# POWER.net
KiCad netlist of a schematic drawn in Altium Designer
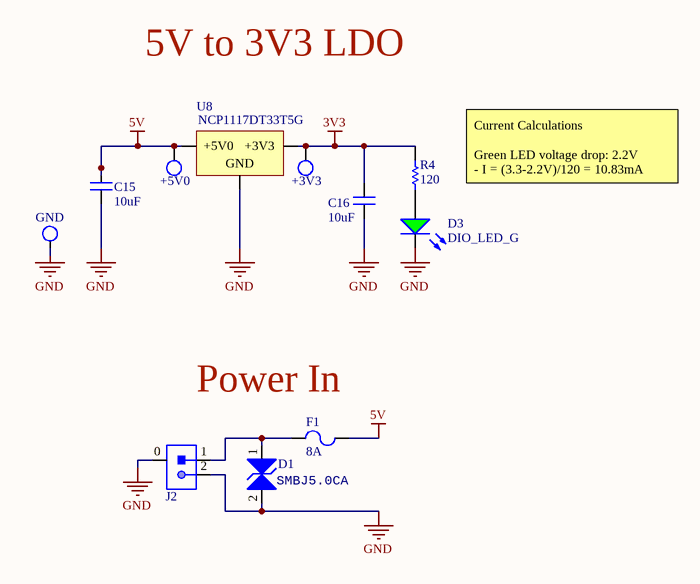
[diagram p0: POWER.SchDoc]

(export (version "E")
  (design (tool "Eeschema 10.0.6"))
  (components
    (comp (ref "+3V3")
      (value "TESTPOINT_LOOP")
      (footprint "TESTPOINT_LOOP")
      (description "Loop testpoint through-hole pad")
      (fields (field (name "MANUFACTURER") "Keystone Electronics"))
      (libsource (lib "UWRT_Schematic_Library_2020") (part "TESTPOINT_LOOP"))
    )
    (comp (ref "+5V0")
      (value "TESTPOINT_LOOP")
      (footprint "TESTPOINT_LOOP")
      (description "Loop testpoint through-hole pad")
      (fields (field (name "MANUFACTURER") "Keystone Electronics"))
      (libsource (lib "UWRT_Schematic_Library_2020") (part "TESTPOINT_LOOP"))
    )
    (comp (ref "C15")
      (value "10uF")
      (footprint "CAPC1206(3216)")
      (description "CAP CER 10UF 50V X5R 1206")
      (fields (field (name "MPN") "GRT31CR61H106KE01L") (field (name "MANUFACTURER") "Murata"))
      (libsource (lib "UWRT_Schematic_Library_2020") (part "CAP_10uF_50V_1206"))
    )
    (comp (ref "C16")
      (value "10uF")
      (footprint "CAPC1206(3216)")
      (description "CAP CER 10UF 50V X5R 1206")
      (fields (field (name "MPN") "GRT31CR61H106KE01L") (field (name "MANUFACTURER") "Murata"))
      (libsource (lib "UWRT_Schematic_Library_2020") (part "CAP_10uF_50V_1206"))
    )
    (comp (ref "D1")
      (value "TVS_DIODE_BIDIRECTIONAL")
      (footprint "TVS_DIODE_BIDIRECTIONAL")
      (description "TVS DIODE 5V 9.2V DO214AA")
      (fields
        (field (name "MANUFACTURER") "Nexperia USA Inc.")
        (field (name "MANUFACTURER PART NUMBER 1") "SMBJ5.0CA")
      )
      (libsource (lib "UWRT_Schematic_Library_2020") (part "TVS_DIODE_BIDIRECTIONAL"))
    )
    (comp (ref "D3")
      (value "DIO_LED_G")
      (footprint "LED_0805_LINE")
      (description "LED GREEN DIFFUSED 0805 SMD")
      (fields (field (name "MPN") "LG R971-KN-1") (field (name "MANUFACTURER") "OSRAM"))
      (libsource (lib "UWRT_Schematic_Library_2020") (part "DIO_LED_G"))
    )
    (comp (ref "F1")
      (value "FUSE_8A_1206")
      (footprint "FUSE_1206")
      (description "FUSE SMD 8A 24V")
      (fields (field (name "CURRENT RATING") "8A"))
      (libsource (lib "UWRT_Schematic_Library_2020") (part "FUSE_8A_1206"))
    )
    (comp (ref "GND")
      (value "TESTPOINT_LOOP")
      (footprint "TESTPOINT_LOOP")
      (description "Loop testpoint through-hole pad")
      (fields (field (name "MANUFACTURER") "Keystone Electronics"))
      (libsource (lib "UWRT_Schematic_Library_2020") (part "TESTPOINT_LOOP"))
    )
    (comp (ref "J2")
      (value "CON_2M_SM_RA")
      (footprint "MOLEX-5024940270")
      (description "CONN HEADER SMD RIGHT ANGLE 2MM PITCH")
      (libsource (lib "UWRT_Schematic_Library_2020") (part "CON_2M_SM_RA"))
    )
    (comp (ref "R4")
      (value "120")
      (footprint "RESC0603(1608)_N")
      (description "RES SMD 120 OHM 5% 1/10W 0603")
      (fields (field (name "TOLERANCE") "5%") (field (name "Comment") "RES_120R_0603"))
      (libsource (lib "UWRT_Schematic_Library_2020") (part "RES_120R_0603"))
    )
    (comp (ref "U8")
      (value "5V0_3V3_LDO")
      (footprint "VOLTAGE_REGULATOR")
      (description "IC REG LINEAR 3.3V 1A DPAK")
      (fields (field (name "MPN") "NCP1117DT33T5G") (field (name "MANUFACTURER") "ON Semiconductor"))
      (libsource (lib "UWRT_Schematic_Library_2020") (part "5V0_3V3_LDO"))
    )
  )
  (nets
    (net (code "1") (name "3V3") (class "Default")
      (node (ref "+3V3") (pin "1") (pintype "passive"))
      (node (ref "C16") (pin "2") (pinfunction "2_2") (pintype "passive"))
      (node (ref "R4") (pin "2") (pinfunction "2_2") (pintype "passive"))
      (node (ref "U8") (pin "2") (pinfunction "+3V3_2") (pintype "passive"))
    )
    (net (code "2") (name "5V") (class "Default")
      (node (ref "+5V0") (pin "1") (pintype "passive"))
      (node (ref "C15") (pin "2") (pinfunction "2_2") (pintype "passive"))
      (node (ref "F1") (pin "2") (pinfunction "2_2") (pintype "passive"))
      (node (ref "U8") (pin "3") (pinfunction "+5V0_3") (pintype "passive"))
    )
    (net (code "3") (name "GND") (class "Default")
      (node (ref "C15") (pin "1") (pinfunction "1_1") (pintype "passive"))
      (node (ref "C16") (pin "1") (pinfunction "1_1") (pintype "passive"))
      (node (ref "D1") (pin "2") (pinfunction "2_2") (pintype "passive"))
      (node (ref "D3") (pin "2") (pinfunction "K_2") (pintype "passive"))
      (node (ref "GND") (pin "1") (pintype "passive"))
      (node (ref "J2") (pin "0") (pinfunction "0_0") (pintype "passive"))
      (node (ref "J2") (pin "2") (pinfunction "2_2") (pintype "passive"))
      (node (ref "U8") (pin "1") (pinfunction "GND_1") (pintype "passive"))
    )
    (net (code "4") (name "Net-(D1-Pad1)") (class "Default")
      (node (ref "D1") (pin "1") (pinfunction "1_1") (pintype "passive"))
      (node (ref "F1") (pin "1") (pinfunction "1_1") (pintype "passive"))
      (node (ref "J2") (pin "1") (pinfunction "1_1") (pintype "passive"))
    )
    (net (code "5") (name "Net-(D3-A)") (class "Default")
      (node (ref "D3") (pin "1") (pinfunction "A_1") (pintype "passive"))
      (node (ref "R4") (pin "1") (pinfunction "1_1") (pintype "passive"))
    )
  )
)
